# current_sense.net
KiCad netlist of a schematic drawn in Altium Designer
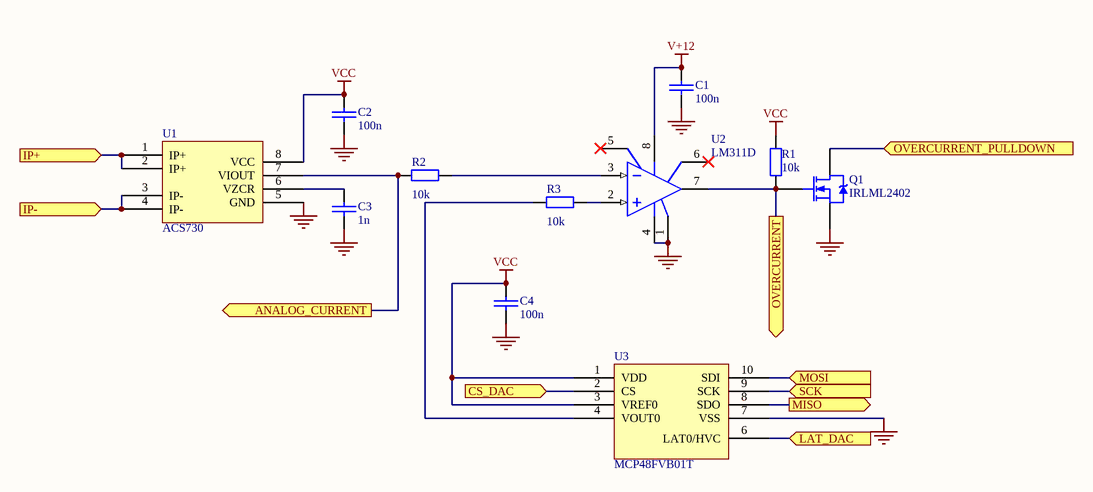
[diagram p0: current_sense.SchDoc]

(export (version "E")
  (design (tool "Eeschema 10.0.6"))
  (components
    (comp (ref "C1")
      (value "100n")
      (footprint "CAPC1608N")
      (description "Capacitor")
      (libsource (lib "*") (part "CAP"))
    )
    (comp (ref "C2")
      (value "100n")
      (footprint "CAPC1608N")
      (description "Capacitor")
      (libsource (lib "*") (part "CAP"))
    )
    (comp (ref "C3")
      (value "1n")
      (footprint "CAPC1608N")
      (description "Capacitor")
      (libsource (lib "*") (part "CAP"))
    )
    (comp (ref "C4")
      (value "100n")
      (footprint "CAPC1608N")
      (description "Capacitor")
      (libsource (lib "*") (part "CAP"))
    )
    (comp (ref "Q1")
      (value "IRLML2402")
      (footprint "SOT-23_N")
      (description "HEXFET Power MOSFET")
      (fields (field (name "PUBLISHER") "Altium Limited"))
      (libsource (lib "IR Discrete MOSFET - Power") (part "IRLML2402"))
    )
    (comp (ref "R1")
      (value "10k")
      (footprint "RESC1608N")
      (description "Resistor")
      (fields (field (name "PUBLISHER") "Altium Limited"))
      (libsource (lib "*") (part "Res2"))
    )
    (comp (ref "R2")
      (value "10k")
      (footprint "RESC1608N")
      (description "Resistor")
      (fields (field (name "PUBLISHER") "Altium Limited"))
      (libsource (lib "") (part "Res2_1"))
    )
    (comp (ref "R3")
      (value "10k")
      (footprint "RESC1608N")
      (description "Resistor")
      (fields (field (name "PUBLISHER") "Altium Limited"))
      (libsource (lib "") (part "Res2_1"))
    )
    (comp (ref "U1") (value "ACS730") (libsource (lib "components") (part "ACS730")))
    (comp (ref "U2")
      (value "LM311D")
      (footprint "SO8_N")
      (description "Voltage Comparator")
      (fields (field (name "PUBLISHER") "Altium Limited"))
      (libsource (lib "ST Analog Comparator") (part "LM311D"))
    )
    (comp (ref "U3") (value "MCP48FVB01T") (libsource (lib "components") (part "MCP48FVB01T")))
  )
  (nets
    (net (code "1") (name "/ANALOG_CURRENT") (class "Default")
      (node (ref "R2") (pin "1") (pinfunction "1_1") (pintype "passive"))
      (node (ref "U1") (pin "7") (pinfunction "VIOUT_7") (pintype "passive"))
    )
    (net (code "2") (name "/CS_DAC") (class "Default")
      (node (ref "U3") (pin "2") (pinfunction "CS_2") (pintype "passive"))
    )
    (net (code "3") (name "/IP+") (class "Default")
      (node (ref "U1") (pin "1") (pinfunction "IP+_1") (pintype "passive"))
      (node (ref "U1") (pin "2") (pinfunction "IP+_2") (pintype "passive"))
    )
    (net (code "4") (name "/IP-") (class "Default")
      (node (ref "U1") (pin "3") (pinfunction "IP-_3") (pintype "passive"))
      (node (ref "U1") (pin "4") (pinfunction "IP-_4") (pintype "passive"))
    )
    (net (code "5") (name "/LAT_DAC") (class "Default")
      (node (ref "U3") (pin "6") (pinfunction "LAT0/HVC_6") (pintype "passive"))
    )
    (net (code "6") (name "/MISO") (class "Default")
      (node (ref "U3") (pin "8") (pinfunction "SDO_8") (pintype "passive"))
    )
    (net (code "7") (name "/MOSI") (class "Default")
      (node (ref "U3") (pin "10") (pinfunction "SDI_10") (pintype "passive"))
    )
    (net (code "8") (name "/OVERCURRENT") (class "Default")
      (node (ref "Q1") (pin "1") (pinfunction "G_1") (pintype "passive"))
      (node (ref "R1") (pin "1") (pinfunction "1_1") (pintype "passive"))
      (node (ref "U2") (pin "7") (pinfunction "OUT_7") (pintype "open_collector"))
    )
    (net (code "9") (name "/OVERCURRENT_PULLDOWN") (class "Default")
      (node (ref "Q1") (pin "3") (pinfunction "D_3") (pintype "passive"))
    )
    (net (code "10") (name "/SCK") (class "Default")
      (node (ref "U3") (pin "9") (pinfunction "SCK_9") (pintype "passive"))
    )
    (net (code "11") (name "GND") (class "Default")
      (node (ref "C1") (pin "1") (pinfunction "1_1") (pintype "passive"))
      (node (ref "C2") (pin "1") (pinfunction "1_1") (pintype "passive"))
      (node (ref "C3") (pin "1") (pinfunction "1_1") (pintype "passive"))
      (node (ref "C4") (pin "1") (pinfunction "1_1") (pintype "passive"))
      (node (ref "Q1") (pin "2") (pinfunction "S_2") (pintype "passive"))
      (node (ref "U1") (pin "5") (pinfunction "GND_5") (pintype "passive"))
      (node (ref "U2") (pin "1") (pinfunction "GND_1") (pintype "power_in"))
      (node (ref "U2") (pin "4") (pinfunction "V-_(CASE)_4") (pintype "power_in"))
      (node (ref "U3") (pin "7") (pinfunction "VSS_7") (pintype "passive"))
    )
    (net (code "12") (name "Net-(U1-VZCR)") (class "Default")
      (node (ref "C3") (pin "2") (pinfunction "2_2") (pintype "passive"))
      (node (ref "U1") (pin "6") (pinfunction "VZCR_6") (pintype "passive"))
    )
    (net (code "13") (name "Net-(U2-IN+)") (class "Default")
      (node (ref "R3") (pin "2") (pinfunction "2_2") (pintype "passive"))
      (node (ref "U2") (pin "2") (pinfunction "IN+_2") (pintype "input"))
    )
    (net (code "14") (name "Net-(U2-IN-)") (class "Default")
      (node (ref "R2") (pin "2") (pinfunction "2_2") (pintype "passive"))
      (node (ref "U2") (pin "3") (pinfunction "IN-_3") (pintype "input"))
    )
    (net (code "15") (name "Net-(U3-VOUT0)") (class "Default")
      (node (ref "R3") (pin "1") (pinfunction "1_1") (pintype "passive"))
      (node (ref "U3") (pin "4") (pinfunction "VOUT0_4") (pintype "passive"))
    )
    (net (code "16") (name "V+12") (class "Default")
      (node (ref "C1") (pin "2") (pinfunction "2_2") (pintype "passive"))
      (node (ref "U2") (pin "8") (pinfunction "V+_8") (pintype "power_in"))
    )
    (net (code "17") (name "VCC") (class "Default")
      (node (ref "C2") (pin "2") (pinfunction "2_2") (pintype "passive"))
      (node (ref "C4") (pin "2") (pinfunction "2_2") (pintype "passive"))
      (node (ref "R1") (pin "2") (pinfunction "2_2") (pintype "passive"))
      (node (ref "U1") (pin "8") (pinfunction "VCC_8") (pintype "passive"))
      (node (ref "U3") (pin "1") (pinfunction "VDD_1") (pintype "passive"))
      (node (ref "U3") (pin "3") (pinfunction "VREF0_3") (pintype "passive"))
    )
    (net (code "18") (name "unconnected-(U2-BAL-Pad5)") (class "Default")
      (node (ref "U2") (pin "5") (pinfunction "BAL_5") (pintype "passive+no_connect"))
    )
    (net (code "19") (name "unconnected-(U2-BAL{slash}STB-Pad6)") (class "Default")
      (node (ref "U2") (pin "6") (pinfunction "BAL/STB_6") (pintype "passive+no_connect"))
    )
  )
)
